# FPGA_IO.net
KiCad netlist of a schematic drawn in Altium Designer
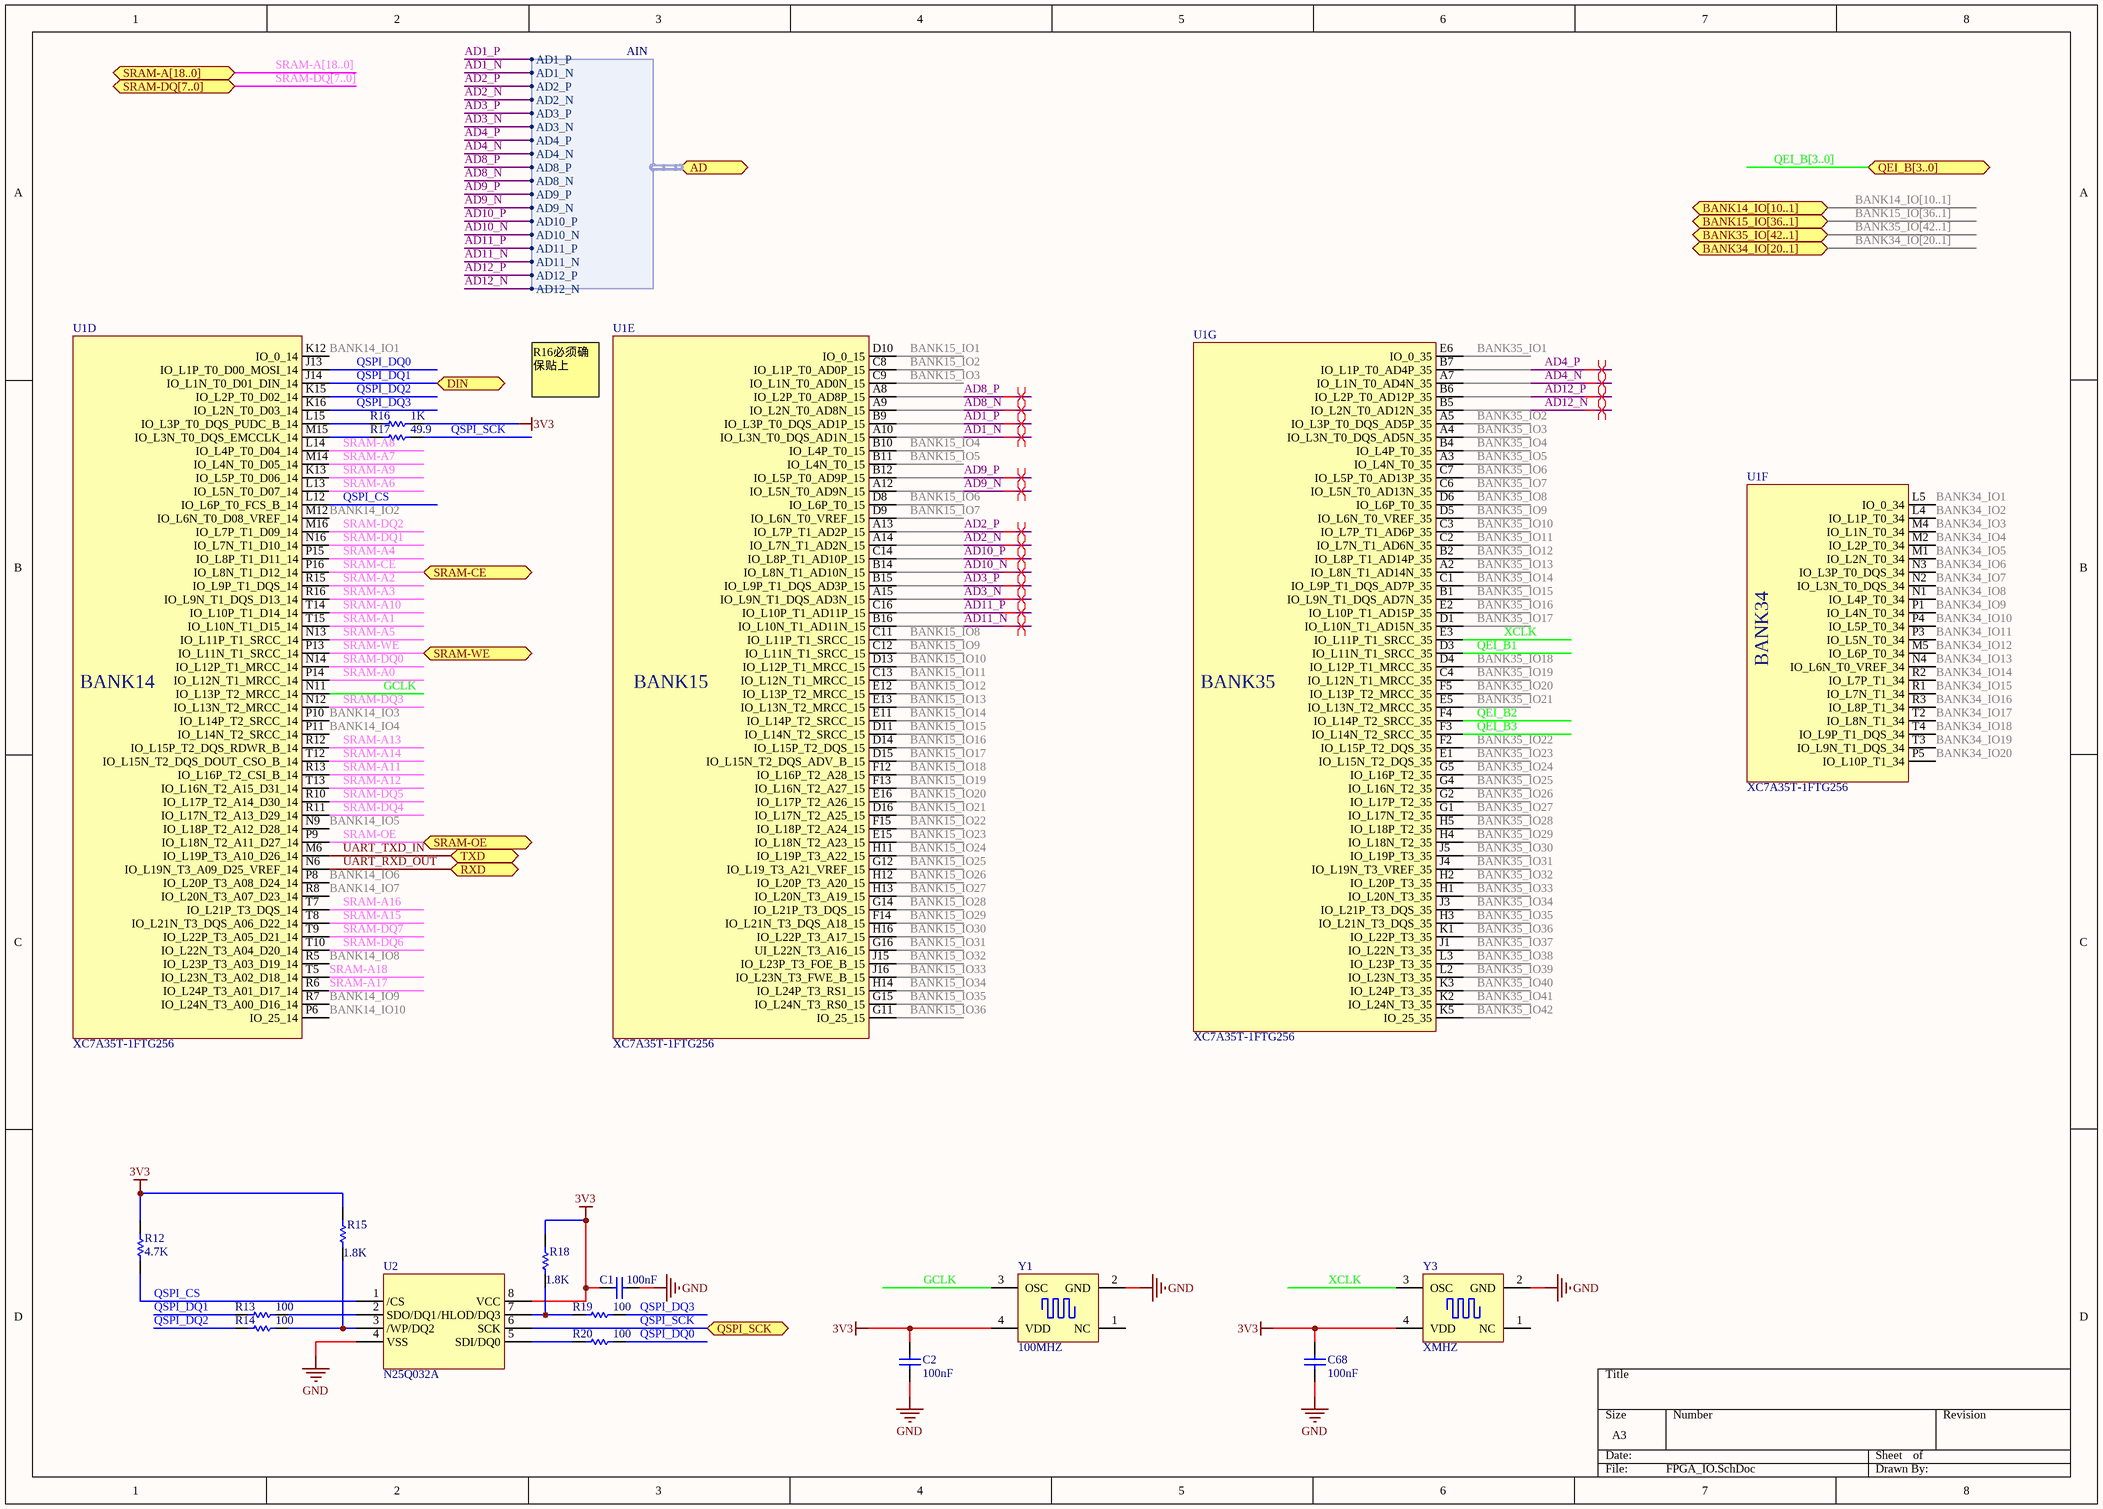
[diagram p0: FPGA_IO.SchDoc]

(export (version "E")
  (design (tool "Eeschema 10.0.6"))
  (components
    (comp (ref "C1")
      (value "100nF")
      (footprint "1608[0603]")
      (description "贴片电容")
      (fields (field (name "Comment") "Cap") (field (name "PUBLISHER") "Altium Limited"))
      (libsource (lib "Sparks") (part "Cap"))
    )
    (comp (ref "C2")
      (value "100nF")
      (footprint "1608[0603]")
      (description "贴片电容")
      (fields (field (name "Comment") "Cap") (field (name "PUBLISHER") "Altium Limited"))
      (libsource (lib "Sparks") (part "Cap"))
    )
    (comp (ref "C68")
      (value "100nF")
      (footprint "1608[0603]")
      (description "贴片电容")
      (fields (field (name "Comment") "Cap") (field (name "PUBLISHER") "Altium Limited"))
      (libsource (lib "Sparks") (part "Cap"))
    )
    (comp (ref "R12")
      (value "4.7K")
      (footprint "1608[0603]")
      (description "贴片电阻")
      (fields (field (name "Comment") "Res") (field (name "PUBLISHER") "Altium Limited"))
      (libsource (lib "Sparks") (part "Res"))
    )
    (comp (ref "R13")
      (value "100")
      (footprint "1608[0603]")
      (description "贴片电阻")
      (fields (field (name "Comment") "Res") (field (name "PUBLISHER") "Altium Limited"))
      (libsource (lib "Sparks") (part "Res"))
    )
    (comp (ref "R14")
      (value "100")
      (footprint "1608[0603]")
      (description "贴片电阻")
      (fields (field (name "Comment") "Res") (field (name "PUBLISHER") "Altium Limited"))
      (libsource (lib "Sparks") (part "Res"))
    )
    (comp (ref "R15")
      (value "1.8K")
      (footprint "1608[0603]")
      (description "贴片电阻")
      (fields (field (name "Comment") "Res") (field (name "PUBLISHER") "Altium Limited"))
      (libsource (lib "Sparks") (part "Res"))
    )
    (comp (ref "R16")
      (value "1K")
      (footprint "1608[0603]")
      (description "贴片电阻")
      (fields (field (name "Comment") "Res") (field (name "PUBLISHER") "Altium Limited"))
      (libsource (lib "Sparks") (part "Res"))
    )
    (comp (ref "R17")
      (value "49.9")
      (footprint "R2012")
      (description "贴片电阻")
      (fields (field (name "Comment") "Res") (field (name "PUBLISHER") "Altium Limited"))
      (libsource (lib "Sparks") (part "Res"))
    )
    (comp (ref "R18")
      (value "1.8K")
      (footprint "1608[0603]")
      (description "贴片电阻")
      (fields (field (name "Comment") "Res") (field (name "PUBLISHER") "Altium Limited"))
      (libsource (lib "Sparks") (part "Res"))
    )
    (comp (ref "R19")
      (value "100")
      (footprint "1608[0603]")
      (description "贴片电阻")
      (fields (field (name "Comment") "Res") (field (name "PUBLISHER") "Altium Limited"))
      (libsource (lib "Sparks") (part "Res"))
    )
    (comp (ref "R20")
      (value "100")
      (footprint "1608[0603]")
      (description "贴片电阻")
      (fields (field (name "Comment") "Res") (field (name "PUBLISHER") "Altium Limited"))
      (libsource (lib "Sparks") (part "Res"))
    )
    (comp (ref "U1")
      (value "XC7A35T-1FTG256")
      (footprint "BGA100P9X9-81A")
      (libsource (lib "Schlib") (part "XC7A35T-1FTG256"))
    )
    (comp (ref "U2")
      (value "N25Q032A")
      (footprint "QFN127P500X600X100_HS-9N")
      (libsource (lib "2号库") (part "N25Q032A"))
    )
    (comp (ref "Y1") (value "100MHZ") (footprint "XTAL7_3225") (libsource (lib "K60-V4.0") (part "XTAL1")))
    (comp (ref "Y3") (value "XMHZ") (footprint "XTAL7_3225") (libsource (lib "K60-V4.0") (part "XTAL1")))
  )
  (nets
    (net (code "3") (name "/AD1_N") (class "Default")
      (node (ref "U1") (pin "A10") (pinfunction "IO_L3N_T0_DQS_AD1N_15_A10") (pintype "passive"))
    )
    (net (code "4") (name "/AD1_P") (class "Default")
      (node (ref "U1") (pin "B9") (pinfunction "IO_L3P_T0_DQS_AD1P_15_B9") (pintype "passive"))
    )
    (net (code "5") (name "/AD2_N") (class "Default")
      (node (ref "U1") (pin "A14") (pinfunction "IO_L7N_T1_AD2N_15_A14") (pintype "passive"))
    )
    (net (code "6") (name "/AD2_P") (class "Default")
      (node (ref "U1") (pin "A13") (pinfunction "IO_L7P_T1_AD2P_15_A13") (pintype "passive"))
    )
    (net (code "7") (name "/AD3_N") (class "Default")
      (node (ref "U1") (pin "A15") (pinfunction "IO_L9N_T1_DQS_AD3N_15_A15") (pintype "passive"))
    )
    (net (code "8") (name "/AD3_P") (class "Default")
      (node (ref "U1") (pin "B15") (pinfunction "IO_L9P_T1_DQS_AD3P_15_B15") (pintype "passive"))
    )
    (net (code "9") (name "/AD4_N") (class "Default")
      (node (ref "U1") (pin "A7") (pinfunction "IO_L1N_T0_AD4N_35_A7") (pintype "passive"))
    )
    (net (code "10") (name "/AD4_P") (class "Default")
      (node (ref "U1") (pin "B7") (pinfunction "IO_L1P_T0_AD4P_35_B7") (pintype "passive"))
    )
    (net (code "11") (name "/AD8_N") (class "Default")
      (node (ref "U1") (pin "A9") (pinfunction "IO_L2N_T0_AD8N_15_A9") (pintype "passive"))
    )
    (net (code "12") (name "/AD8_P") (class "Default")
      (node (ref "U1") (pin "A8") (pinfunction "IO_L2P_T0_AD8P_15_A8") (pintype "passive"))
    )
    (net (code "13") (name "/AD9_N") (class "Default")
      (node (ref "U1") (pin "A12") (pinfunction "IO_L5N_T0_AD9N_15_A12") (pintype "passive"))
    )
    (net (code "14") (name "/AD9_P") (class "Default")
      (node (ref "U1") (pin "B12") (pinfunction "IO_L5P_T0_AD9P_15_B12") (pintype "passive"))
    )
    (net (code "15") (name "/AD10_N") (class "Default")
      (node (ref "U1") (pin "B14") (pinfunction "IO_L8N_T1_AD10N_15_B14") (pintype "passive"))
    )
    (net (code "16") (name "/AD10_P") (class "Default")
      (node (ref "U1") (pin "C14") (pinfunction "IO_L8P_T1_AD10P_15_C14") (pintype "passive"))
    )
    (net (code "17") (name "/AD11_N") (class "Default")
      (node (ref "U1") (pin "B16") (pinfunction "IO_L10N_T1_AD11N_15_B16") (pintype "passive"))
    )
    (net (code "18") (name "/AD11_P") (class "Default")
      (node (ref "U1") (pin "C16") (pinfunction "IO_L10P_T1_AD11P_15_C16") (pintype "passive"))
    )
    (net (code "19") (name "/AD12_N") (class "Default")
      (node (ref "U1") (pin "B5") (pinfunction "IO_L2N_T0_AD12N_35_B5") (pintype "passive"))
    )
    (net (code "20") (name "/AD12_P") (class "Default")
      (node (ref "U1") (pin "B6") (pinfunction "IO_L2P_T0_AD12P_35_B6") (pintype "passive"))
    )
    (net (code "21") (name "/BANK14_IO1") (class "Default")
      (node (ref "U1") (pin "K12") (pinfunction "IO_0_14_K12") (pintype "passive"))
    )
    (net (code "22") (name "/BANK14_IO2") (class "Default")
      (node (ref "U1") (pin "M12") (pinfunction "IO_L6N_T0_D08_VREF_14_M12") (pintype "passive"))
    )
    (net (code "23") (name "/BANK14_IO3") (class "Default")
      (node (ref "U1") (pin "P10") (pinfunction "IO_L14P_T2_SRCC_14_P10") (pintype "passive"))
    )
    (net (code "24") (name "/BANK14_IO4") (class "Default")
      (node (ref "U1") (pin "P11") (pinfunction "IO_L14N_T2_SRCC_14_P11") (pintype "passive"))
    )
    (net (code "25") (name "/BANK14_IO5") (class "Default")
      (node (ref "U1") (pin "N9") (pinfunction "IO_L18P_T2_A12_D28_14_N9") (pintype "passive"))
    )
    (net (code "26") (name "/BANK14_IO6") (class "Default")
      (node (ref "U1") (pin "P8") (pinfunction "IO_L20P_T3_A08_D24_14_P8") (pintype "passive"))
    )
    (net (code "27") (name "/BANK14_IO7") (class "Default")
      (node (ref "U1") (pin "R8") (pinfunction "IO_L20N_T3_A07_D23_14_R8") (pintype "passive"))
    )
    (net (code "28") (name "/BANK14_IO8") (class "Default")
      (node (ref "U1") (pin "R5") (pinfunction "IO_L23P_T3_A03_D19_14_R5") (pintype "passive"))
    )
    (net (code "29") (name "/BANK14_IO9") (class "Default")
      (node (ref "U1") (pin "R7") (pinfunction "IO_L24N_T3_A00_D16_14_R7") (pintype "passive"))
    )
    (net (code "30") (name "/BANK14_IO10") (class "Default")
      (node (ref "U1") (pin "P6") (pinfunction "IO_25_14_P6") (pintype "passive"))
    )
    (net (code "32") (name "/BANK15_IO1") (class "Default")
      (node (ref "U1") (pin "D10") (pinfunction "IO_0_15_D10") (pintype "passive"))
    )
    (net (code "33") (name "/BANK15_IO2") (class "Default")
      (node (ref "U1") (pin "C8") (pinfunction "IO_L1P_T0_AD0P_15_C8") (pintype "passive"))
    )
    (net (code "34") (name "/BANK15_IO3") (class "Default")
      (node (ref "U1") (pin "C9") (pinfunction "IO_L1N_T0_AD0N_15_C9") (pintype "passive"))
    )
    (net (code "35") (name "/BANK15_IO4") (class "Default")
      (node (ref "U1") (pin "B10") (pinfunction "IO_L4P_T0_15_B10") (pintype "passive"))
    )
    (net (code "36") (name "/BANK15_IO5") (class "Default")
      (node (ref "U1") (pin "B11") (pinfunction "IO_L4N_T0_15_B11") (pintype "passive"))
    )
    (net (code "37") (name "/BANK15_IO6") (class "Default")
      (node (ref "U1") (pin "D8") (pinfunction "IO_L6P_T0_15_D8") (pintype "passive"))
    )
    (net (code "38") (name "/BANK15_IO7") (class "Default")
      (node (ref "U1") (pin "D9") (pinfunction "IO_L6N_T0_VREF_15_D9") (pintype "passive"))
    )
    (net (code "39") (name "/BANK15_IO8") (class "Default")
      (node (ref "U1") (pin "C11") (pinfunction "IO_L11P_T1_SRCC_15_C11") (pintype "passive"))
    )
    (net (code "40") (name "/BANK15_IO9") (class "Default")
      (node (ref "U1") (pin "C12") (pinfunction "IO_L11N_T1_SRCC_15_C12") (pintype "passive"))
    )
    (net (code "41") (name "/BANK15_IO10") (class "Default")
      (node (ref "U1") (pin "D13") (pinfunction "IO_L12P_T1_MRCC_15_D13") (pintype "passive"))
    )
    (net (code "42") (name "/BANK15_IO11") (class "Default")
      (node (ref "U1") (pin "C13") (pinfunction "IO_L12N_T1_MRCC_15_C13") (pintype "passive"))
    )
    (net (code "43") (name "/BANK15_IO12") (class "Default")
      (node (ref "U1") (pin "E12") (pinfunction "IO_L13P_T2_MRCC_15_E12") (pintype "passive"))
    )
    (net (code "44") (name "/BANK15_IO13") (class "Default")
      (node (ref "U1") (pin "E13") (pinfunction "IO_L13N_T2_MRCC_15_E13") (pintype "passive"))
    )
    (net (code "45") (name "/BANK15_IO14") (class "Default")
      (node (ref "U1") (pin "E11") (pinfunction "IO_L14P_T2_SRCC_15_E11") (pintype "passive"))
    )
    (net (code "46") (name "/BANK15_IO15") (class "Default")
      (node (ref "U1") (pin "D11") (pinfunction "IO_L14N_T2_SRCC_15_D11") (pintype "passive"))
    )
    (net (code "47") (name "/BANK15_IO16") (class "Default")
      (node (ref "U1") (pin "D14") (pinfunction "IO_L15P_T2_DQS_15_D14") (pintype "passive"))
    )
    (net (code "48") (name "/BANK15_IO17") (class "Default")
      (node (ref "U1") (pin "D15") (pinfunction "IO_L15N_T2_DQS_ADV_B_15_D15") (pintype "passive"))
    )
    (net (code "49") (name "/BANK15_IO18") (class "Default")
      (node (ref "U1") (pin "F12") (pinfunction "IO_L16P_T2_A28_15_F12") (pintype "passive"))
    )
    (net (code "50") (name "/BANK15_IO19") (class "Default")
      (node (ref "U1") (pin "F13") (pinfunction "IO_L16N_T2_A27_15_F13") (pintype "passive"))
    )
    (net (code "51") (name "/BANK15_IO20") (class "Default")
      (node (ref "U1") (pin "E16") (pinfunction "IO_L17P_T2_A26_15_E16") (pintype "passive"))
    )
    (net (code "52") (name "/BANK15_IO21") (class "Default")
      (node (ref "U1") (pin "D16") (pinfunction "IO_L17N_T2_A25_15_D16") (pintype "passive"))
    )
    (net (code "53") (name "/BANK15_IO22") (class "Default")
      (node (ref "U1") (pin "F15") (pinfunction "IO_L18P_T2_A24_15_F15") (pintype "passive"))
    )
    (net (code "54") (name "/BANK15_IO23") (class "Default")
      (node (ref "U1") (pin "E15") (pinfunction "IO_L18N_T2_A23_15_E15") (pintype "passive"))
    )
    (net (code "55") (name "/BANK15_IO24") (class "Default")
      (node (ref "U1") (pin "H11") (pinfunction "IO_L19P_T3_A22_15_H11") (pintype "passive"))
    )
    (net (code "56") (name "/BANK15_IO25") (class "Default")
      (node (ref "U1") (pin "G12") (pinfunction "IO_L19_T3_A21_VREF_15_G12") (pintype "passive"))
    )
    (net (code "57") (name "/BANK15_IO26") (class "Default")
      (node (ref "U1") (pin "H12") (pinfunction "IO_L20P_T3_A20_15_H12") (pintype "passive"))
    )
    (net (code "58") (name "/BANK15_IO27") (class "Default")
      (node (ref "U1") (pin "H13") (pinfunction "IO_L20N_T3_A19_15_H13") (pintype "passive"))
    )
    (net (code "59") (name "/BANK15_IO28") (class "Default")
      (node (ref "U1") (pin "G14") (pinfunction "IO_L21P_T3_DQS_15_G14") (pintype "passive"))
    )
    (net (code "60") (name "/BANK15_IO29") (class "Default")
      (node (ref "U1") (pin "F14") (pinfunction "IO_L21N_T3_DQS_A18_15_F14") (pintype "passive"))
    )
    (net (code "61") (name "/BANK15_IO30") (class "Default")
      (node (ref "U1") (pin "H16") (pinfunction "IO_L22P_T3_A17_15_H16") (pintype "passive"))
    )
    (net (code "62") (name "/BANK15_IO31") (class "Default")
      (node (ref "U1") (pin "G16") (pinfunction "UI_L22N_T3_A16_15_G16") (pintype "passive"))
    )
    (net (code "63") (name "/BANK15_IO32") (class "Default")
      (node (ref "U1") (pin "J15") (pinfunction "IO_L23P_T3_FOE_B_15_J15") (pintype "passive"))
    )
    (net (code "64") (name "/BANK15_IO33") (class "Default")
      (node (ref "U1") (pin "J16") (pinfunction "IO_L23N_T3_FWE_B_15_J16") (pintype "passive"))
    )
    (net (code "65") (name "/BANK15_IO34") (class "Default")
      (node (ref "U1") (pin "H14") (pinfunction "IO_L24P_T3_RS1_15_H14") (pintype "passive"))
    )
    (net (code "66") (name "/BANK15_IO35") (class "Default")
      (node (ref "U1") (pin "G15") (pinfunction "IO_L24N_T3_RS0_15_G15") (pintype "passive"))
    )
    (net (code "67") (name "/BANK15_IO36") (class "Default")
      (node (ref "U1") (pin "G11") (pinfunction "IO_25_15_G11") (pintype "passive"))
    )
    (net (code "69") (name "/BANK34_IO1") (class "Default")
      (node (ref "U1") (pin "L5") (pinfunction "IO_0_34_L5") (pintype "passive"))
    )
    (net (code "70") (name "/BANK34_IO2") (class "Default")
      (node (ref "U1") (pin "L4") (pinfunction "IO_L1P_T0_34_L4") (pintype "passive"))
    )
    (net (code "71") (name "/BANK34_IO3") (class "Default")
      (node (ref "U1") (pin "M4") (pinfunction "IO_L1N_T0_34_M4") (pintype "passive"))
    )
    (net (code "72") (name "/BANK34_IO4") (class "Default")
      (node (ref "U1") (pin "M2") (pinfunction "IO_L2P_T0_34_M2") (pintype "passive"))
    )
    (net (code "73") (name "/BANK34_IO5") (class "Default")
      (node (ref "U1") (pin "M1") (pinfunction "IO_L2N_T0_34_M1") (pintype "passive"))
    )
    (net (code "74") (name "/BANK34_IO6") (class "Default")
      (node (ref "U1") (pin "N3") (pinfunction "IO_L3P_T0_DQS_34_N3") (pintype "passive"))
    )
    (net (code "75") (name "/BANK34_IO7") (class "Default")
      (node (ref "U1") (pin "N2") (pinfunction "IO_L3N_T0_DQS_34_N2") (pintype "passive"))
    )
    (net (code "76") (name "/BANK34_IO8") (class "Default")
      (node (ref "U1") (pin "N1") (pinfunction "IO_L4P_T0_34_N1") (pintype "passive"))
    )
    (net (code "77") (name "/BANK34_IO9") (class "Default")
      (node (ref "U1") (pin "P1") (pinfunction "IO_L4N_T0_34_P1") (pintype "passive"))
    )
    (net (code "78") (name "/BANK34_IO10") (class "Default")
      (node (ref "U1") (pin "P4") (pinfunction "IO_L5P_T0_34_P4") (pintype "passive"))
    )
    (net (code "79") (name "/BANK34_IO11") (class "Default")
      (node (ref "U1") (pin "P3") (pinfunction "IO_L5N_T0_34_P3") (pintype "passive"))
    )
    (net (code "80") (name "/BANK34_IO12") (class "Default")
      (node (ref "U1") (pin "M5") (pinfunction "IO_L6P_T0_34_M5") (pintype "passive"))
    )
    (net (code "81") (name "/BANK34_IO13") (class "Default")
      (node (ref "U1") (pin "N4") (pinfunction "IO_L6N_T0_VREF_34_N4") (pintype "passive"))
    )
    (net (code "82") (name "/BANK34_IO14") (class "Default")
      (node (ref "U1") (pin "R2") (pinfunction "IO_L7P_T1_34_R2") (pintype "passive"))
    )
    (net (code "83") (name "/BANK34_IO15") (class "Default")
      (node (ref "U1") (pin "R1") (pinfunction "IO_L7N_T1_34_R1") (pintype "passive"))
    )
    (net (code "84") (name "/BANK34_IO16") (class "Default")
      (node (ref "U1") (pin "R3") (pinfunction "IO_L8P_T1_34_R3") (pintype "passive"))
    )
    (net (code "85") (name "/BANK34_IO17") (class "Default")
      (node (ref "U1") (pin "T2") (pinfunction "IO_L8N_T1_34_T2") (pintype "passive"))
    )
    (net (code "86") (name "/BANK34_IO18") (class "Default")
      (node (ref "U1") (pin "T4") (pinfunction "IO_L9P_T1_DQS_34_T4") (pintype "passive"))
    )
    (net (code "87") (name "/BANK34_IO19") (class "Default")
      (node (ref "U1") (pin "T3") (pinfunction "IO_L9N_T1_DQS_34_T3") (pintype "passive"))
    )
    (net (code "88") (name "/BANK34_IO20") (class "Default")
      (node (ref "U1") (pin "P5") (pinfunction "IO_L10P_T1_34_P5") (pintype "passive"))
    )
    (net (code "90") (name "/BANK35_IO1") (class "Default")
      (node (ref "U1") (pin "E6") (pinfunction "IO_0_35_E6") (pintype "passive"))
    )
    (net (code "91") (name "/BANK35_IO2") (class "Default")
      (node (ref "U1") (pin "A5") (pinfunction "IO_L3P_T0_DQS_AD5P_35_A5") (pintype "passive"))
    )
    (net (code "92") (name "/BANK35_IO3") (class "Default")
      (node (ref "U1") (pin "A4") (pinfunction "IO_L3N_T0_DQS_AD5N_35_A4") (pintype "passive"))
    )
    (net (code "93") (name "/BANK35_IO4") (class "Default")
      (node (ref "U1") (pin "B4") (pinfunction "IO_L4P_T0_35_B4") (pintype "passive"))
    )
    (net (code "94") (name "/BANK35_IO5") (class "Default")
      (node (ref "U1") (pin "A3") (pinfunction "IO_L4N_T0_35_A3") (pintype "passive"))
    )
    (net (code "95") (name "/BANK35_IO6") (class "Default")
      (node (ref "U1") (pin "C7") (pinfunction "IO_L5P_T0_AD13P_35_C7") (pintype "passive"))
    )
    (net (code "96") (name "/BANK35_IO7") (class "Default")
      (node (ref "U1") (pin "C6") (pinfunction "IO_L5N_T0_AD13N_35_C6") (pintype "passive"))
    )
    (net (code "97") (name "/BANK35_IO8") (class "Default")
      (node (ref "U1") (pin "D6") (pinfunction "IO_L6P_T0_35_D6") (pintype "passive"))
    )
    (net (code "98") (name "/BANK35_IO9") (class "Default")
      (node (ref "U1") (pin "D5") (pinfunction "IO_L6N_T0_VREF_35_D5") (pintype "passive"))
    )
    (net (code "99") (name "/BANK35_IO10") (class "Default")
      (node (ref "U1") (pin "C3") (pinfunction "IO_L7P_T1_AD6P_35_C3") (pintype "passive"))
    )
    (net (code "100") (name "/BANK35_IO11") (class "Default")
      (node (ref "U1") (pin "C2") (pinfunction "IO_L7N_T1_AD6N_35_C2") (pintype "passive"))
    )
    (net (code "101") (name "/BANK35_IO12") (class "Default")
      (node (ref "U1") (pin "B2") (pinfunction "IO_L8P_T1_AD14P_35_B2") (pintype "passive"))
    )
    (net (code "102") (name "/BANK35_IO13") (class "Default")
      (node (ref "U1") (pin "A2") (pinfunction "IO_L8N_T1_AD14N_35_A2") (pintype "passive"))
    )
    (net (code "103") (name "/BANK35_IO14") (class "Default")
      (node (ref "U1") (pin "C1") (pinfunction "IO_L9P_T1_DQS_AD7P_35_C1") (pintype "passive"))
    )
    (net (code "104") (name "/BANK35_IO15") (class "Default")
      (node (ref "U1") (pin "B1") (pinfunction "IO_L9N_T1_DQS_AD7N_35_B1") (pintype "passive"))
    )
    (net (code "105") (name "/BANK35_IO16") (class "Default")
      (node (ref "U1") (pin "E2") (pinfunction "IO_L10P_T1_AD15P_35_E2") (pintype "passive"))
    )
    (net (code "106") (name "/BANK35_IO17") (class "Default")
      (node (ref "U1") (pin "D1") (pinfunction "IO_L10N_T1_AD15N_35_D1") (pintype "passive"))
    )
    (net (code "107") (name "/BANK35_IO18") (class "Default")
      (node (ref "U1") (pin "D4") (pinfunction "IO_L12P_T1_MRCC_35_D4") (pintype "passive"))
    )
    (net (code "108") (name "/BANK35_IO19") (class "Default")
      (node (ref "U1") (pin "C4") (pinfunction "IO_L12N_T1_MRCC_35_C4") (pintype "passive"))
    )
    (net (code "109") (name "/BANK35_IO20") (class "Default")
      (node (ref "U1") (pin "F5") (pinfunction "IO_L13P_T2_MRCC_35_F5") (pintype "passive"))
    )
    (net (code "110") (name "/BANK35_IO21") (class "Default")
      (node (ref "U1") (pin "E5") (pinfunction "IO_L13N_T2_MRCC_35_E5") (pintype "passive"))
    )
    (net (code "111") (name "/BANK35_IO22") (class "Default")
      (node (ref "U1") (pin "F2") (pinfunction "IO_L15P_T2_DQS_35_F2") (pintype "passive"))
    )
    (net (code "112") (name "/BANK35_IO23") (class "Default")
      (node (ref "U1") (pin "E1") (pinfunction "IO_L15N_T2_DQS_35_E1") (pintype "passive"))
    )
    (net (code "113") (name "/BANK35_IO24") (class "Default")
      (node (ref "U1") (pin "G5") (pinfunction "IO_L16P_T2_35_G5") (pintype "passive"))
    )
    (net (code "114") (name "/BANK35_IO25") (class "Default")
      (node (ref "U1") (pin "G4") (pinfunction "IO_L16N_T2_35_G4") (pintype "passive"))
    )
    (net (code "115") (name "/BANK35_IO26") (class "Default")
      (node (ref "U1") (pin "G2") (pinfunction "IO_L17P_T2_35_G2") (pintype "passive"))
    )
    (net (code "116") (name "/BANK35_IO27") (class "Default")
      (node (ref "U1") (pin "G1") (pinfunction "IO_L17N_T2_35_G1") (pintype "passive"))
    )
    (net (code "117") (name "/BANK35_IO28") (class "Default")
      (node (ref "U1") (pin "H5") (pinfunction "IO_L18P_T2_35_H5") (pintype "passive"))
    )
    (net (code "118") (name "/BANK35_IO29") (class "Default")
      (node (ref "U1") (pin "H4") (pinfunction "IO_L18N_T2_35_H4") (pintype "passive"))
    )
    (net (code "119") (name "/BANK35_IO30") (class "Default")
      (node (ref "U1") (pin "J5") (pinfunction "IO_L19P_T3_35_J5") (pintype "passive"))
    )
    (net (code "120") (name "/BANK35_IO31") (class "Default")
      (node (ref "U1") (pin "J4") (pinfunction "IO_L19N_T3_VREF_35_J4") (pintype "passive"))
    )
    (net (code "121") (name "/BANK35_IO32") (class "Default")
      (node (ref "U1") (pin "H2") (pinfunction "IO_L20P_T3_35_H2") (pintype "passive"))
    )
    (net (code "122") (name "/BANK35_IO33") (class "Default")
      (node (ref "U1") (pin "H1") (pinfunction "IO_L20N_T3_35_H1") (pintype "passive"))
    )
    (net (code "123") (name "/BANK35_IO34") (class "Default")
      (node (ref "U1") (pin "J3") (pinfunction "IO_L21P_T3_DQS_35_J3") (pintype "passive"))
    )
    (net (code "124") (name "/BANK35_IO35") (class "Default")
      (node (ref "U1") (pin "H3") (pinfunction "IO_L21N_T3_DQS_35_H3") (pintype "passive"))
    )
    (net (code "125") (name "/BANK35_IO36") (class "Default")
      (node (ref "U1") (pin "K1") (pinfunction "IO_L22P_T3_35_K1") (pintype "passive"))
    )
    (net (code "126") (name "/BANK35_IO37") (class "Default")
      (node (ref "U1") (pin "J1") (pinfunction "IO_L22N_T3_35_J1") (pintype "passive"))
    )
    (net (code "127") (name "/BANK35_IO38") (class "Default")
      (node (ref "U1") (pin "L3") (pinfunction "IO_L23P_T3_35_L3") (pintype "passive"))
    )
    (net (code "128") (name "/BANK35_IO39") (class "Default")
      (node (ref "U1") (pin "L2") (pinfunction "IO_L23N_T3_35_L2") (pintype "passive"))
    )
    (net (code "129") (name "/BANK35_IO40") (class "Default")
      (node (ref "U1") (pin "K3") (pinfunction "IO_L24P_T3_35_K3") (pintype "passive"))
    )
    (net (code "130") (name "/BANK35_IO41") (class "Default")
      (node (ref "U1") (pin "K2") (pinfunction "IO_L24N_T3_35_K2") (pintype "passive"))
    )
    (net (code "131") (name "/BANK35_IO42") (class "Default")
      (node (ref "U1") (pin "K5") (pinfunction "IO_25_35_K5") (pintype "passive"))
    )
    (net (code "133") (name "/GCLK") (class "Default")
      (node (ref "U1") (pin "N11") (pinfunction "IO_L13P_T2_MRCC_14_N11") (pintype "passive"))
      (node (ref "Y1") (pin "3") (pinfunction "OSC_3") (pintype "passive"))
    )
    (net (code "134") (name "/QEI_B1") (class "Default")
      (node (ref "U1") (pin "D3") (pinfunction "IO_L11N_T1_SRCC_35_D3") (pintype "passive"))
    )
    (net (code "135") (name "/QEI_B2") (class "Default")
      (node (ref "U1") (pin "F4") (pinfunction "IO_L14P_T2_SRCC_35_F4") (pintype "passive"))
    )
    (net (code "136") (name "/QEI_B3") (class "Default")
      (node (ref "U1") (pin "F3") (pinfunction "IO_L14N_T2_SRCC_35_F3") (pintype "passive"))
    )
    (net (code "138") (name "/QSPI_CS") (class "Default")
      (node (ref "R12") (pin "2") (pinfunction "2_2") (pintype "passive"))
      (node (ref "U1") (pin "L12") (pinfunction "IO_L6P_T0_FCS_B_14_L12") (pintype "passive"))
      (node (ref "U2") (pin "1") (pinfunction "/CS_1") (pintype "passive"))
    )
    (net (code "139") (name "/QSPI_DQ0") (class "Default")
      (node (ref "R20") (pin "1") (pinfunction "1_1") (pintype "passive"))
      (node (ref "U1") (pin "J13") (pinfunction "IO_L1P_T0_D00_MOSI_14_J13") (pintype "passive"))
    )
    (net (code "140") (name "/QSPI_DQ1") (class "Default")
      (node (ref "R13") (pin "2") (pinfunction "2_2") (pintype "passive"))
      (node (ref "U1") (pin "J14") (pinfunction "IO_L1N_T0_D01_DIN_14_J14") (pintype "passive"))
    )
    (net (code "141") (name "/QSPI_DQ2") (class "Default")
      (node (ref "R14") (pin "2") (pinfunction "2_2") (pintype "passive"))
      (node (ref "U1") (pin "K15") (pinfunction "IO_L2P_T0_D02_14_K15") (pintype "passive"))
    )
    (net (code "142") (name "/QSPI_DQ3") (class "Default")
      (node (ref "R19") (pin "1") (pinfunction "1_1") (pintype "passive"))
      (node (ref "U1") (pin "K16") (pinfunction "IO_L2N_T0_D03_14_K16") (pintype "passive"))
    )
    (net (code "143") (name "/QSPI_SCK") (class "Default")
      (node (ref "R17") (pin "1") (pinfunction "1_1") (pintype "passive"))
      (node (ref "U2") (pin "6") (pinfunction "SCK_6") (pintype "passive"))
    )
    (net (code "144") (name "/SRAM-A0") (class "Default")
      (node (ref "U1") (pin "P14") (pinfunction "IO_L12N_T1_MRCC_14_P14") (pintype "passive"))
    )
    (net (code "145") (name "/SRAM-A1") (class "Default")
      (node (ref "U1") (pin "T15") (pinfunction "IO_L10N_T1_D15_14_T15") (pintype "passive"))
    )
    (net (code "146") (name "/SRAM-A2") (class "Default")
      (node (ref "U1") (pin "R15") (pinfunction "IO_L9P_T1_DQS_14_R15") (pintype "passive"))
    )
    (net (code "147") (name "/SRAM-A3") (class "Default")
      (node (ref "U1") (pin "R16") (pinfunction "IO_L9N_T1_DQS_D13_14_R16") (pintype "passive"))
    )
    (net (code "148") (name "/SRAM-A4") (class "Default")
      (node (ref "U1") (pin "P15") (pinfunction "IO_L8P_T1_D11_14_P15") (pintype "passive"))
    )
    (net (code "149") (name "/SRAM-A5") (class "Default")
      (node (ref "U1") (pin "N13") (pinfunction "IO_L11P_T1_SRCC_14_N13") (pintype "passive"))
    )
    (net (code "150") (name "/SRAM-A6") (class "Default")
      (node (ref "U1") (pin "L13") (pinfunction "IO_L5N_T0_D07_14_L13") (pintype "passive"))
    )
    (net (code "151") (name "/SRAM-A7") (class "Default")
      (node (ref "U1") (pin "M14") (pinfunction "IO_L4N_T0_D05_14_M14") (pintype "passive"))
    )
    (net (code "152") (name "/SRAM-A8") (class "Default")
      (node (ref "U1") (pin "L14") (pinfunction "IO_L4P_T0_D04_14_L14") (pintype "passive"))
    )
    (net (code "153") (name "/SRAM-A9") (class "Default")
      (node (ref "U1") (pin "K13") (pinfunction "IO_L5P_T0_D06_14_K13") (pintype "passive"))
    )
    (net (code "154") (name "/SRAM-A10") (class "Default")
      (node (ref "U1") (pin "T14") (pinfunction "IO_L10P_T1_D14_14_T14") (pintype "passive"))
    )
    (net (code "155") (name "/SRAM-A11") (class "Default")
      (node (ref "U1") (pin "R13") (pinfunction "IO_L16P_T2_CSI_B_14_R13") (pintype "passive"))
    )
    (net (code "156") (name "/SRAM-A12") (class "Default")
      (node (ref "U1") (pin "T13") (pinfunction "IO_L16N_T2_A15_D31_14_T13") (pintype "passive"))
    )
    (net (code "157") (name "/SRAM-A13") (class "Default")
      (node (ref "U1") (pin "R12") (pinfunction "IO_L15P_T2_DQS_RDWR_B_14_R12") (pintype "passive"))
    )
    (net (code "158") (name "/SRAM-A14") (class "Default")
      (node (ref "U1") (pin "T12") (pinfunction "IO_L15N_T2_DQS_DOUT_CSO_B_14_T12") (pintype "passive"))
    )
    (net (code "159") (name "/SRAM-A15") (class "Default")
      (node (ref "U1") (pin "T8") (pinfunction "IO_L21N_T3_DQS_A06_D22_14_T8") (pintype "passive"))
    )
    (net (code "160") (name "/SRAM-A16") (class "Default")
      (node (ref "U1") (pin "T7") (pinfunction "IO_L21P_T3_DQS_14_T7") (pintype "passive"))
    )
    (net (code "161") (name "/SRAM-A17") (class "Default")
      (node (ref "U1") (pin "R6") (pinfunction "IO_L24P_T3_A01_D17_14_R6") (pintype "passive"))
    )
    (net (code "162") (name "/SRAM-A18") (class "Default")
      (node (ref "U1") (pin "T5") (pinfunction "IO_L23N_T3_A02_D18_14_T5") (pintype "passive"))
    )
    (net (code "164") (name "/SRAM-CE") (class "Default")
      (node (ref "U1") (pin "P16") (pinfunction "IO_L8N_T1_D12_14_P16") (pintype "passive"))
    )
    (net (code "165") (name "/SRAM-DQ0") (class "Default")
      (node (ref "U1") (pin "N14") (pinfunction "IO_L12P_T1_MRCC_14_N14") (pintype "passive"))
    )
    (net (code "166") (name "/SRAM-DQ1") (class "Default")
      (node (ref "U1") (pin "N16") (pinfunction "IO_L7N_T1_D10_14_N16") (pintype "passive"))
    )
    (net (code "167") (name "/SRAM-DQ2") (class "Default")
      (node (ref "U1") (pin "M16") (pinfunction "IO_L7P_T1_D09_14_M16") (pintype "passive"))
    )
    (net (code "168") (name "/SRAM-DQ3") (class "Default")
      (node (ref "U1") (pin "N12") (pinfunction "IO_L13N_T2_MRCC_14_N12") (pintype "passive"))
    )
    (net (code "169") (name "/SRAM-DQ4") (class "Default")
      (node (ref "U1") (pin "R11") (pinfunction "IO_L17N_T2_A13_D29_14_R11") (pintype "passive"))
    )
    (net (code "170") (name "/SRAM-DQ5") (class "Default")
      (node (ref "U1") (pin "R10") (pinfunction "IO_L17P_T2_A14_D30_14_R10") (pintype "passive"))
    )
    (net (code "171") (name "/SRAM-DQ6") (class "Default")
      (node (ref "U1") (pin "T10") (pinfunction "IO_L22N_T3_A04_D20_14_T10") (pintype "passive"))
    )
    (net (code "172") (name "/SRAM-DQ7") (class "Default")
      (node (ref "U1") (pin "T9") (pinfunction "IO_L22P_T3_A05_D21_14_T9") (pintype "passive"))
    )
    (net (code "174") (name "/SRAM-OE") (class "Default")
      (node (ref "U1") (pin "P9") (pinfunction "IO_L18N_T2_A11_D27_14_P9") (pintype "passive"))
    )
    (net (code "175") (name "/SRAM-WE") (class "Default")
      (node (ref "U1") (pin "P13") (pinfunction "IO_L11N_T1_SRCC_14_P13") (pintype "passive"))
    )
    (net (code "176") (name "/UART_RXD_OUT") (class "Default")
      (node (ref "U1") (pin "N6") (pinfunction "IO_L19N_T3_A09_D25_VREF_14_N6") (pintype "passive"))
    )
    (net (code "177") (name "/UART_TXD_IN") (class "Default")
      (node (ref "U1") (pin "M6") (pinfunction "IO_L19P_T3_A10_D26_14_M6") (pintype "passive"))
    )
    (net (code "178") (name "/XCLK") (class "Default")
      (node (ref "U1") (pin "E3") (pinfunction "IO_L11P_T1_SRCC_35_E3") (pintype "passive"))
      (node (ref "Y3") (pin "3") (pinfunction "OSC_3") (pintype "passive"))
    )
    (net (code "180") (name "3V3") (class "Default")
      (node (ref "C1") (pin "1") (pinfunction "1_1") (pintype "passive"))
      (node (ref "C2") (pin "2") (pinfunction "2_2") (pintype "passive"))
      (node (ref "C68") (pin "2") (pinfunction "2_2") (pintype "passive"))
      (node (ref "R12") (pin "1") (pinfunction "1_1") (pintype "passive"))
      (node (ref "R15") (pin "1") (pinfunction "1_1") (pintype "passive"))
      (node (ref "R16") (pin "1") (pinfunction "1_1") (pintype "passive"))
      (node (ref "R18") (pin "1") (pinfunction "1_1") (pintype "passive"))
      (node (ref "U2") (pin "8") (pinfunction "VCC_8") (pintype "passive"))
      (node (ref "Y1") (pin "4") (pinfunction "VDD_4") (pintype "passive"))
      (node (ref "Y3") (pin "4") (pinfunction "VDD_4") (pintype "passive"))
    )
    (net (code "181") (name "GND") (class "Default")
      (node (ref "C1") (pin "2") (pinfunction "2_2") (pintype "passive"))
      (node (ref "C2") (pin "1") (pinfunction "1_1") (pintype "passive"))
      (node (ref "C68") (pin "1") (pinfunction "1_1") (pintype "passive"))
      (node (ref "U2") (pin "4") (pinfunction "VSS_4") (pintype "passive"))
      (node (ref "Y1") (pin "2") (pinfunction "GND_2") (pintype "passive"))
      (node (ref "Y3") (pin "2") (pinfunction "GND_2") (pintype "passive"))
    )
    (net (code "182") (name "Net-(U1D-IO_L3N_T0_DQS_EMCCLK_14)") (class "Default")
      (node (ref "R17") (pin "2") (pinfunction "2_2") (pintype "passive"))
      (node (ref "U1") (pin "M15") (pinfunction "IO_L3N_T0_DQS_EMCCLK_14_M15") (pintype "passive"))
    )
    (net (code "183") (name "Net-(U1D-IO_L3P_T0_DQS_PUDC_B_14)") (class "Default")
      (node (ref "R16") (pin "2") (pinfunction "2_2") (pintype "passive"))
      (node (ref "U1") (pin "L15") (pinfunction "IO_L3P_T0_DQS_PUDC_B_14_L15") (pintype "passive"))
    )
    (net (code "184") (name "Net-(U2-SDI{slash}DQ0)") (class "Default")
      (node (ref "R20") (pin "2") (pinfunction "2_2") (pintype "passive"))
      (node (ref "U2") (pin "5") (pinfunction "SDI/DQ0_5") (pintype "passive"))
    )
    (net (code "185") (name "Net-(U2-SDO{slash}DQ1)") (class "Default")
      (node (ref "R13") (pin "1") (pinfunction "1_1") (pintype "passive"))
      (node (ref "U2") (pin "2") (pinfunction "SDO/DQ1_2") (pintype "passive"))
    )
    (net (code "186") (name "Net-(U2-{slash}HLOD{slash}DQ3)") (class "Default")
      (node (ref "R18") (pin "2") (pinfunction "2_2") (pintype "passive"))
      (node (ref "R19") (pin "2") (pinfunction "2_2") (pintype "passive"))
      (node (ref "U2") (pin "7") (pinfunction "/HLOD/DQ3_7") (pintype "passive"))
    )
    (net (code "187") (name "Net-(U2-{slash}WP{slash}DQ2)") (class "Default")
      (node (ref "R14") (pin "1") (pinfunction "1_1") (pintype "passive"))
      (node (ref "R15") (pin "2") (pinfunction "2_2") (pintype "passive"))
      (node (ref "U2") (pin "3") (pinfunction "/WP/DQ2_3") (pintype "passive"))
    )
    (net (code "188") (name "unconnected-(Y1-NC-Pad1)") (class "Default")
      (node (ref "Y1") (pin "1") (pinfunction "NC_1") (pintype "passive"))
    )
    (net (code "189") (name "unconnected-(Y3-NC-Pad1)") (class "Default")
      (node (ref "Y3") (pin "1") (pinfunction "NC_1") (pintype "passive"))
    )
  )
)
